# sulamatikV3.net
KiCad netlist of a schematic drawn in EAGLE
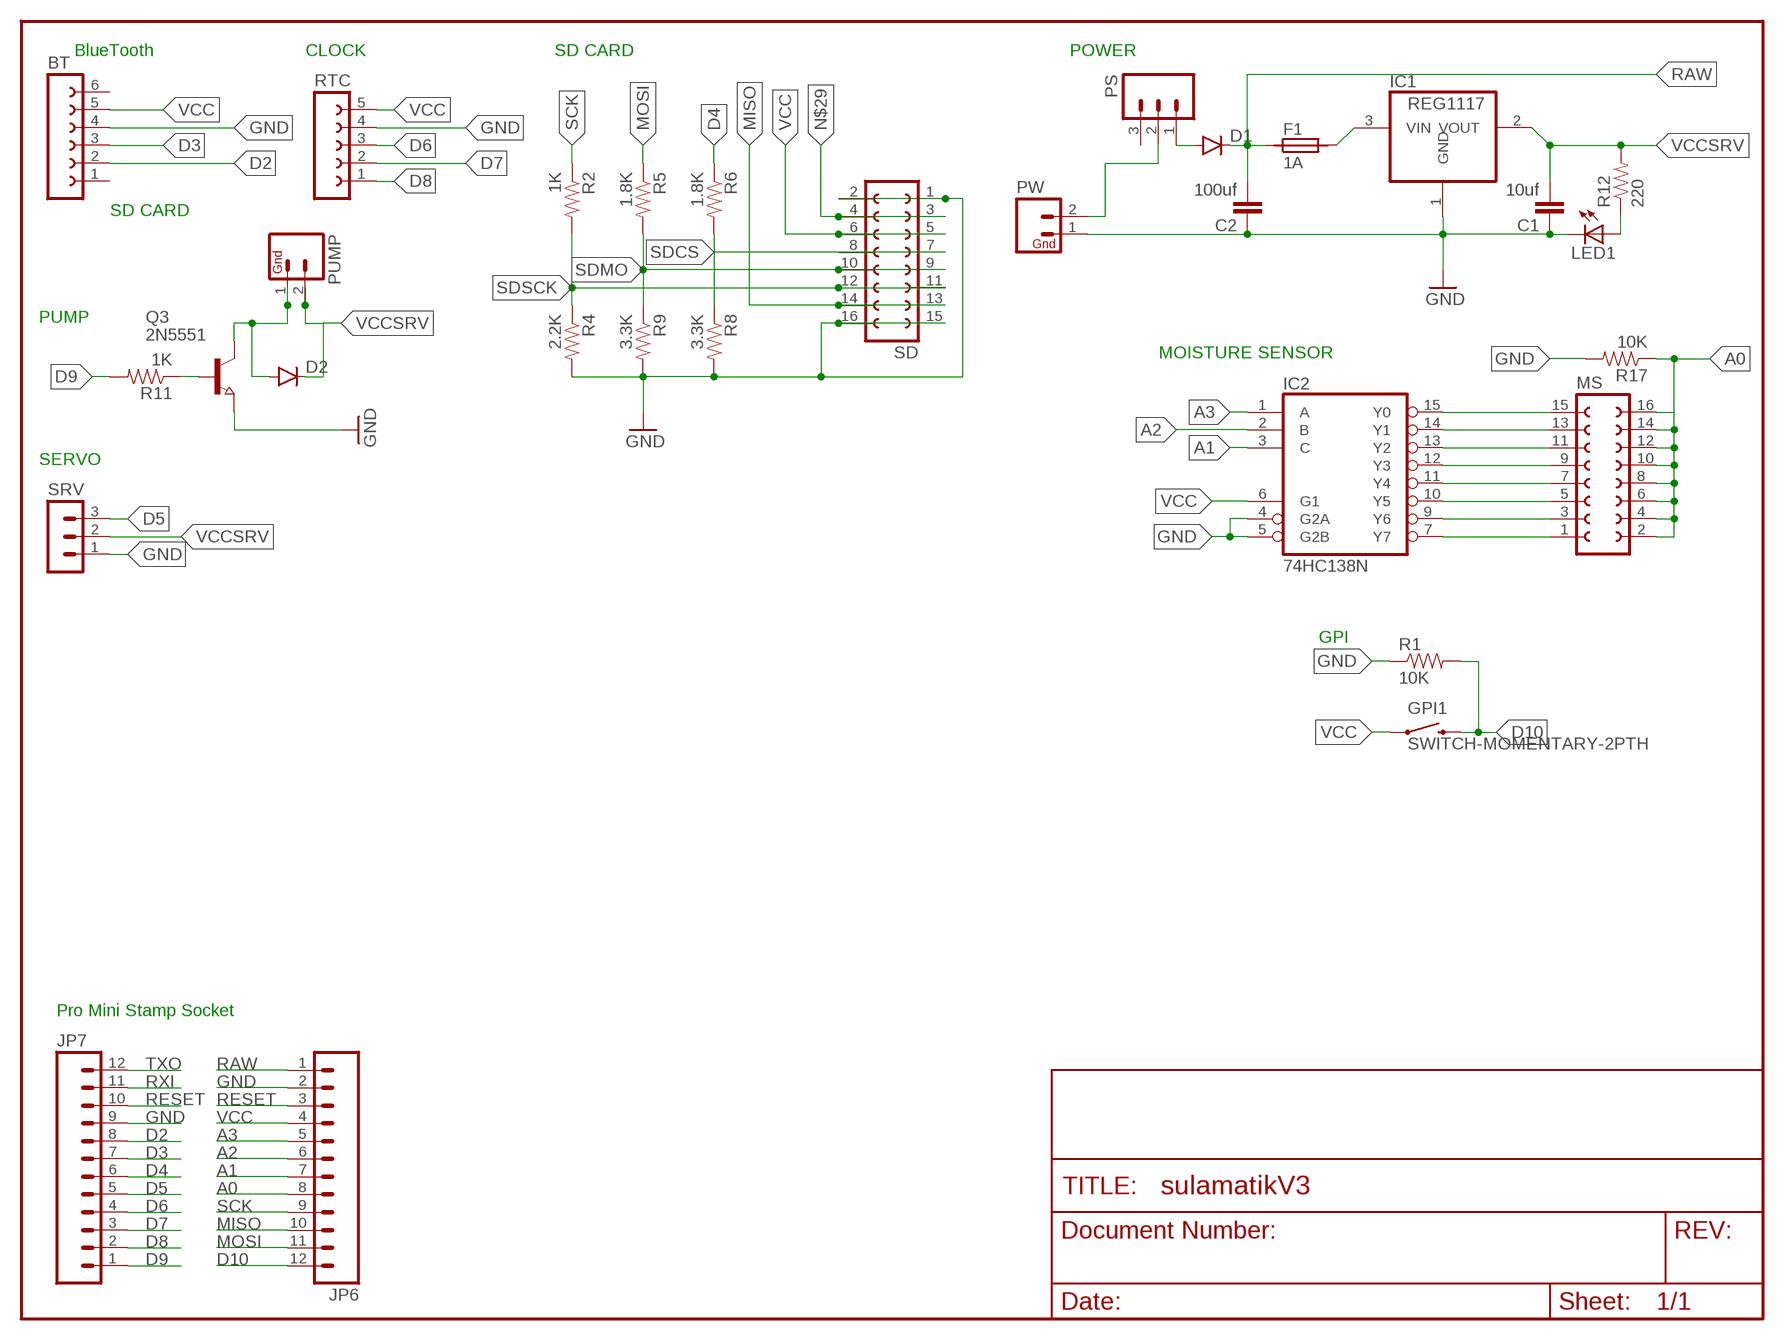
[diagram p0: schematic, sheet 1]

(export (version "E")
  (design (tool "Eeschema 10.0.6"))
  (components
    (comp (ref "BT")
      (value "FE06-1")
      (footprint "eagle-import:FE06")
      (libsource (lib "eagle-import") (part "FE06-1"))
    )
    (comp (ref "C1")
      (value "10uf")
      (footprint "eagle-import:0805")
      (libsource (lib "eagle-import") (part "CAP0805"))
    )
    (comp (ref "C2")
      (value "100uf")
      (footprint "eagle-import:0805")
      (libsource (lib "eagle-import") (part "CAP0805"))
    )
    (comp (ref "D1")
      (value "DIODESMA")
      (footprint "eagle-import:SMA-DIODE")
      (libsource (lib "eagle-import") (part "DIODESMA"))
    )
    (comp (ref "D2")
      (value "DIODESMA")
      (footprint "eagle-import:SMA-DIODE")
      (libsource (lib "eagle-import") (part "DIODESMA"))
    )
    (comp (ref "F1")
      (value "1A")
      (footprint "eagle-import:1820")
      (libsource (lib "eagle-import") (part "SIBA194600"))
    )
    (comp (ref "GPI1")
      (value "SWITCH-MOMENTARY-2PTH")
      (footprint "eagle-import:TACTILE-PTH")
      (libsource (lib "eagle-import") (part "SWITCH-MOMENTARY-2PTH"))
    )
    (comp (ref "IC1")
      (value "REG1117")
      (footprint "eagle-import:SOT223")
      (libsource (lib "eagle-import") (part "REG1117"))
    )
    (comp (ref "IC2")
      (value "74HC138N")
      (footprint "eagle-import:DIL16")
      (libsource (lib "eagle-import") (part "74138NHC"))
    )
    (comp (ref "JP6")
      (value "M12PTH")
      (footprint "eagle-import:1X12")
      (libsource (lib "eagle-import") (part "M12PTH"))
    )
    (comp (ref "JP7")
      (value "M12PTH")
      (footprint "eagle-import:1X12")
      (libsource (lib "eagle-import") (part "M12PTH"))
    )
    (comp (ref "LED1")
      (value "LEDCHIP-LED0805")
      (footprint "eagle-import:CHIP-LED0805")
      (libsource (lib "eagle-import") (part "LEDCHIP-LED0805"))
    )
    (comp (ref "MS")
      (value "FE08-2")
      (footprint "eagle-import:FE08-2")
      (libsource (lib "eagle-import") (part "FE08-2"))
    )
    (comp (ref "PS")
      (value "M03PTH")
      (footprint "eagle-import:1X03")
      (libsource (lib "eagle-import") (part "M03PTH"))
    )
    (comp (ref "PUMP")
      (value "M02PTH")
      (footprint "eagle-import:1X02")
      (libsource (lib "eagle-import") (part "M02PTH"))
    )
    (comp (ref "PW")
      (value "M02PTH")
      (footprint "eagle-import:1X02")
      (libsource (lib "eagle-import") (part "M02PTH"))
    )
    (comp (ref "Q3")
      (value "2N5551")
      (footprint "eagle-import:SOT23")
      (libsource (lib "eagle-import") (part "NPN-TRANSISTOR_SOT23"))
    )
    (comp (ref "R1")
      (value "10K")
      (footprint "eagle-import:0805")
      (libsource (lib "eagle-import") (part "RESISTOR0805-RES"))
    )
    (comp (ref "R2")
      (value "1K")
      (footprint "eagle-import:0805")
      (libsource (lib "eagle-import") (part "RESISTOR0805-RES"))
    )
    (comp (ref "R4")
      (value "2.2K")
      (footprint "eagle-import:0805")
      (libsource (lib "eagle-import") (part "RESISTOR0805-RES"))
    )
    (comp (ref "R5")
      (value "1.8K")
      (footprint "eagle-import:0805")
      (libsource (lib "eagle-import") (part "RESISTOR0805-RES"))
    )
    (comp (ref "R6")
      (value "1.8K")
      (footprint "eagle-import:0805")
      (libsource (lib "eagle-import") (part "RESISTOR0805-RES"))
    )
    (comp (ref "R8")
      (value "3.3K")
      (footprint "eagle-import:0805")
      (libsource (lib "eagle-import") (part "RESISTOR0805-RES"))
    )
    (comp (ref "R9")
      (value "3.3K")
      (footprint "eagle-import:0805")
      (libsource (lib "eagle-import") (part "RESISTOR0805-RES"))
    )
    (comp (ref "R11")
      (value "1K")
      (footprint "eagle-import:0805")
      (libsource (lib "eagle-import") (part "RESISTOR0805-RES"))
    )
    (comp (ref "R12")
      (value "220")
      (footprint "eagle-import:0805")
      (libsource (lib "eagle-import") (part "RESISTOR0805-RES"))
    )
    (comp (ref "R17")
      (value "10K")
      (footprint "eagle-import:0805")
      (libsource (lib "eagle-import") (part "RESISTOR0805-RES"))
    )
    (comp (ref "RTC")
      (value "FE05-1")
      (footprint "eagle-import:FE05-1")
      (libsource (lib "eagle-import") (part "FE05-1"))
    )
    (comp (ref "SD")
      (value "FE08-2")
      (footprint "eagle-import:FE08-2")
      (libsource (lib "eagle-import") (part "FE08-2"))
    )
    (comp (ref "SRV")
      (value "MA03-1")
      (footprint "eagle-import:MA03-1")
      (libsource (lib "eagle-import") (part "MA03-1"))
    )
  )
  (nets
    (net (code "1") (name "/RESET") (class "Default")
      (node (ref "JP6") (pin "3") (pinfunction "3_3") (pintype "passive"))
      (node (ref "JP7") (pin "10") (pinfunction "10_10") (pintype "passive"))
    )
    (net (code "2") (name "/RXI") (class "Default")
      (node (ref "JP7") (pin "11") (pinfunction "11_11") (pintype "passive"))
    )
    (net (code "3") (name "/TXO") (class "Default")
      (node (ref "JP7") (pin "12") (pinfunction "12_12") (pintype "passive"))
    )
    (net (code "4") (name "A0") (class "Default")
      (node (ref "JP6") (pin "8") (pinfunction "8_8") (pintype "passive"))
      (node (ref "MS") (pin "10") (pinfunction "10_10") (pintype "passive"))
      (node (ref "MS") (pin "12") (pinfunction "12_12") (pintype "passive"))
      (node (ref "MS") (pin "14") (pinfunction "14_14") (pintype "passive"))
      (node (ref "MS") (pin "16") (pinfunction "16_16") (pintype "passive"))
      (node (ref "MS") (pin "2") (pinfunction "2_2") (pintype "passive"))
      (node (ref "MS") (pin "4") (pinfunction "4_4") (pintype "passive"))
      (node (ref "MS") (pin "6") (pinfunction "6_6") (pintype "passive"))
      (node (ref "MS") (pin "8") (pinfunction "8_8") (pintype "passive"))
      (node (ref "R17") (pin "1") (pinfunction "1_1") (pintype "passive"))
    )
    (net (code "5") (name "A1") (class "Default")
      (node (ref "IC2") (pin "3") (pinfunction "C_3") (pintype "input"))
      (node (ref "JP6") (pin "7") (pinfunction "7_7") (pintype "passive"))
    )
    (net (code "6") (name "A2") (class "Default")
      (node (ref "IC2") (pin "2") (pinfunction "B_2") (pintype "input"))
      (node (ref "JP6") (pin "6") (pinfunction "6_6") (pintype "passive"))
    )
    (net (code "7") (name "A3") (class "Default")
      (node (ref "IC2") (pin "1") (pinfunction "A_1") (pintype "input"))
      (node (ref "JP6") (pin "5") (pinfunction "5_5") (pintype "passive"))
    )
    (net (code "8") (name "D2") (class "Default")
      (node (ref "BT") (pin "2") (pinfunction "2_2") (pintype "passive"))
      (node (ref "JP7") (pin "8") (pinfunction "8_8") (pintype "passive"))
    )
    (net (code "9") (name "D3") (class "Default")
      (node (ref "BT") (pin "3") (pinfunction "3_3") (pintype "passive"))
      (node (ref "JP7") (pin "7") (pinfunction "7_7") (pintype "passive"))
    )
    (net (code "10") (name "D4") (class "Default")
      (node (ref "JP7") (pin "6") (pinfunction "6_6") (pintype "passive"))
      (node (ref "R6") (pin "1") (pinfunction "1_1") (pintype "passive"))
    )
    (net (code "11") (name "D5") (class "Default")
      (node (ref "JP7") (pin "5") (pinfunction "5_5") (pintype "passive"))
      (node (ref "SRV") (pin "3") (pinfunction "3_3") (pintype "passive"))
    )
    (net (code "12") (name "D6") (class "Default")
      (node (ref "JP7") (pin "4") (pinfunction "4_4") (pintype "passive"))
      (node (ref "RTC") (pin "3") (pinfunction "3_3") (pintype "passive"))
    )
    (net (code "13") (name "D7") (class "Default")
      (node (ref "JP7") (pin "3") (pinfunction "3_3") (pintype "passive"))
      (node (ref "RTC") (pin "2") (pinfunction "2_2") (pintype "passive"))
    )
    (net (code "14") (name "D8") (class "Default")
      (node (ref "JP7") (pin "2") (pinfunction "2_2") (pintype "passive"))
      (node (ref "RTC") (pin "1") (pinfunction "1_1") (pintype "passive"))
    )
    (net (code "15") (name "D9") (class "Default")
      (node (ref "JP7") (pin "1") (pinfunction "1_1") (pintype "passive"))
      (node (ref "R11") (pin "2") (pinfunction "2_2") (pintype "passive"))
    )
    (net (code "16") (name "D10") (class "Default")
      (node (ref "GPI1") (pin "3") (pinfunction "2_3") (pintype "passive"))
      (node (ref "JP6") (pin "12") (pinfunction "12_12") (pintype "passive"))
      (node (ref "R1") (pin "2") (pinfunction "2_2") (pintype "passive"))
    )
    (net (code "17") (name "GND") (class "Default")
      (node (ref "BT") (pin "4") (pinfunction "4_4") (pintype "passive"))
      (node (ref "C1") (pin "1") (pinfunction "1_1") (pintype "passive"))
      (node (ref "C2") (pin "1") (pinfunction "1_1") (pintype "passive"))
      (node (ref "IC1") (pin "1") (pinfunction "GND_1") (pintype "power_in"))
      (node (ref "IC2") (pin "4") (pinfunction "G2A_4") (pintype "input"))
      (node (ref "IC2") (pin "5") (pinfunction "G2B_5") (pintype "input"))
      (node (ref "JP6") (pin "2") (pinfunction "2_2") (pintype "passive"))
      (node (ref "JP7") (pin "9") (pinfunction "9_9") (pintype "passive"))
      (node (ref "LED1") (pin "C") (pinfunction "C_C") (pintype "passive"))
      (node (ref "PW") (pin "1") (pinfunction "1_1") (pintype "passive"))
      (node (ref "Q3") (pin "2") (pinfunction "E_2") (pintype "passive"))
      (node (ref "R1") (pin "1") (pinfunction "1_1") (pintype "passive"))
      (node (ref "R17") (pin "2") (pinfunction "2_2") (pintype "passive"))
      (node (ref "R4") (pin "2") (pinfunction "2_2") (pintype "passive"))
      (node (ref "R8") (pin "2") (pinfunction "2_2") (pintype "passive"))
      (node (ref "R9") (pin "2") (pinfunction "2_2") (pintype "passive"))
      (node (ref "RTC") (pin "4") (pinfunction "4_4") (pintype "passive"))
      (node (ref "SD") (pin "1") (pinfunction "1_1") (pintype "passive"))
      (node (ref "SD") (pin "15") (pinfunction "15_15") (pintype "passive"))
      (node (ref "SD") (pin "16") (pinfunction "16_16") (pintype "passive"))
      (node (ref "SD") (pin "2") (pinfunction "2_2") (pintype "passive"))
      (node (ref "SRV") (pin "1") (pinfunction "1_1") (pintype "passive"))
    )
    (net (code "18") (name "MISO") (class "Default")
      (node (ref "JP6") (pin "10") (pinfunction "10_10") (pintype "passive"))
      (node (ref "SD") (pin "13") (pinfunction "13_13") (pintype "passive"))
      (node (ref "SD") (pin "14") (pinfunction "14_14") (pintype "passive"))
    )
    (net (code "19") (name "MOSI") (class "Default")
      (node (ref "JP6") (pin "11") (pinfunction "11_11") (pintype "passive"))
      (node (ref "R5") (pin "1") (pinfunction "1_1") (pintype "passive"))
    )
    (net (code "20") (name "N$29") (class "Default")
      (node (ref "SD") (pin "3") (pinfunction "3_3") (pintype "passive"))
      (node (ref "SD") (pin "4") (pinfunction "4_4") (pintype "passive"))
    )
    (net (code "21") (name "Net-(D1-PadA)") (class "Default")
      (node (ref "D1") (pin "A") (pinfunction "A_A") (pintype "passive"))
      (node (ref "PS") (pin "1") (pinfunction "1_1") (pintype "passive"))
    )
    (net (code "22") (name "Net-(IC1-VIN)") (class "Default")
      (node (ref "F1") (pin "2") (pinfunction "2_2") (pintype "passive"))
      (node (ref "IC1") (pin "3") (pinfunction "VIN_3") (pintype "input"))
    )
    (net (code "23") (name "Net-(IC2A-Y0)") (class "Default")
      (node (ref "IC2") (pin "15") (pinfunction "Y0_15") (pintype "output"))
      (node (ref "MS") (pin "15") (pinfunction "15_15") (pintype "passive"))
    )
    (net (code "24") (name "Net-(IC2A-Y1)") (class "Default")
      (node (ref "IC2") (pin "14") (pinfunction "Y1_14") (pintype "output"))
      (node (ref "MS") (pin "13") (pinfunction "13_13") (pintype "passive"))
    )
    (net (code "25") (name "Net-(IC2A-Y2)") (class "Default")
      (node (ref "IC2") (pin "13") (pinfunction "Y2_13") (pintype "output"))
      (node (ref "MS") (pin "11") (pinfunction "11_11") (pintype "passive"))
    )
    (net (code "26") (name "Net-(IC2A-Y3)") (class "Default")
      (node (ref "IC2") (pin "12") (pinfunction "Y3_12") (pintype "output"))
      (node (ref "MS") (pin "9") (pinfunction "9_9") (pintype "passive"))
    )
    (net (code "27") (name "Net-(IC2A-Y4)") (class "Default")
      (node (ref "IC2") (pin "11") (pinfunction "Y4_11") (pintype "output"))
      (node (ref "MS") (pin "7") (pinfunction "7_7") (pintype "passive"))
    )
    (net (code "28") (name "Net-(IC2A-Y5)") (class "Default")
      (node (ref "IC2") (pin "10") (pinfunction "Y5_10") (pintype "output"))
      (node (ref "MS") (pin "5") (pinfunction "5_5") (pintype "passive"))
    )
    (net (code "29") (name "Net-(IC2A-Y6)") (class "Default")
      (node (ref "IC2") (pin "9") (pinfunction "Y6_9") (pintype "output"))
      (node (ref "MS") (pin "3") (pinfunction "3_3") (pintype "passive"))
    )
    (net (code "30") (name "Net-(IC2A-Y7)") (class "Default")
      (node (ref "IC2") (pin "7") (pinfunction "Y7_7") (pintype "output"))
      (node (ref "MS") (pin "1") (pinfunction "1_1") (pintype "passive"))
    )
    (net (code "31") (name "Net-(LED1-PadA)") (class "Default")
      (node (ref "LED1") (pin "A") (pinfunction "A_A") (pintype "passive"))
      (node (ref "R12") (pin "1") (pinfunction "1_1") (pintype "passive"))
    )
    (net (code "32") (name "Net-(PS-Pad2)") (class "Default")
      (node (ref "PS") (pin "2") (pinfunction "2_2") (pintype "passive"))
      (node (ref "PW") (pin "2") (pinfunction "2_2") (pintype "passive"))
    )
    (net (code "33") (name "Net-(Q3-B)") (class "Default")
      (node (ref "Q3") (pin "1") (pinfunction "B_1") (pintype "passive"))
      (node (ref "R11") (pin "1") (pinfunction "1_1") (pintype "passive"))
    )
    (net (code "34") (name "Net-(Q3-C)") (class "Default")
      (node (ref "D2") (pin "A") (pinfunction "A_A") (pintype "passive"))
      (node (ref "PUMP") (pin "1") (pinfunction "1_1") (pintype "passive"))
      (node (ref "Q3") (pin "3") (pinfunction "C_3") (pintype "passive"))
    )
    (net (code "35") (name "RAW") (class "Default")
      (node (ref "C2") (pin "2") (pinfunction "2_2") (pintype "passive"))
      (node (ref "D1") (pin "C") (pinfunction "C_C") (pintype "passive"))
      (node (ref "F1") (pin "1") (pinfunction "1_1") (pintype "passive"))
      (node (ref "JP6") (pin "1") (pinfunction "1_1") (pintype "passive"))
    )
    (net (code "36") (name "SCK") (class "Default")
      (node (ref "JP6") (pin "9") (pinfunction "9_9") (pintype "passive"))
      (node (ref "R2") (pin "1") (pinfunction "1_1") (pintype "passive"))
    )
    (net (code "37") (name "SDCS") (class "Default")
      (node (ref "R6") (pin "2") (pinfunction "2_2") (pintype "passive"))
      (node (ref "R8") (pin "1") (pinfunction "1_1") (pintype "passive"))
      (node (ref "SD") (pin "7") (pinfunction "7_7") (pintype "passive"))
      (node (ref "SD") (pin "8") (pinfunction "8_8") (pintype "passive"))
    )
    (net (code "38") (name "SDMO") (class "Default")
      (node (ref "R5") (pin "2") (pinfunction "2_2") (pintype "passive"))
      (node (ref "R9") (pin "1") (pinfunction "1_1") (pintype "passive"))
      (node (ref "SD") (pin "10") (pinfunction "10_10") (pintype "passive"))
      (node (ref "SD") (pin "9") (pinfunction "9_9") (pintype "passive"))
    )
    (net (code "39") (name "SDSCK") (class "Default")
      (node (ref "R2") (pin "2") (pinfunction "2_2") (pintype "passive"))
      (node (ref "R4") (pin "1") (pinfunction "1_1") (pintype "passive"))
      (node (ref "SD") (pin "11") (pinfunction "11_11") (pintype "passive"))
      (node (ref "SD") (pin "12") (pinfunction "12_12") (pintype "passive"))
    )
    (net (code "40") (name "VCC") (class "Default")
      (node (ref "BT") (pin "5") (pinfunction "5_5") (pintype "passive"))
      (node (ref "GPI1") (pin "1") (pinfunction "1_1") (pintype "passive"))
      (node (ref "IC2") (pin "6") (pinfunction "G1_6") (pintype "input"))
      (node (ref "JP6") (pin "4") (pinfunction "4_4") (pintype "passive"))
      (node (ref "RTC") (pin "5") (pinfunction "5_5") (pintype "passive"))
      (node (ref "SD") (pin "5") (pinfunction "5_5") (pintype "passive"))
      (node (ref "SD") (pin "6") (pinfunction "6_6") (pintype "passive"))
    )
    (net (code "41") (name "VCCSRV") (class "Default")
      (node (ref "C1") (pin "2") (pinfunction "2_2") (pintype "passive"))
      (node (ref "D2") (pin "C") (pinfunction "C_C") (pintype "passive"))
      (node (ref "IC1") (pin "2") (pinfunction "VOUT_2") (pintype "output"))
      (node (ref "PUMP") (pin "2") (pinfunction "2_2") (pintype "passive"))
      (node (ref "R12") (pin "2") (pinfunction "2_2") (pintype "passive"))
      (node (ref "SRV") (pin "2") (pinfunction "2_2") (pintype "passive"))
    )
    (net (code "42") (name "unconnected-(BT-Pad1)") (class "Default")
      (node (ref "BT") (pin "1") (pinfunction "1_1") (pintype "passive"))
    )
    (net (code "43") (name "unconnected-(BT-Pad6)") (class "Default")
      (node (ref "BT") (pin "6") (pinfunction "6_6") (pintype "passive"))
    )
    (net (code "44") (name "unconnected-(PS-Pad3)") (class "Default")
      (node (ref "PS") (pin "3") (pinfunction "3_3") (pintype "passive"))
    )
  )
)
